# ft600.net
KiCad netlist of a schematic drawn in Altium Designer
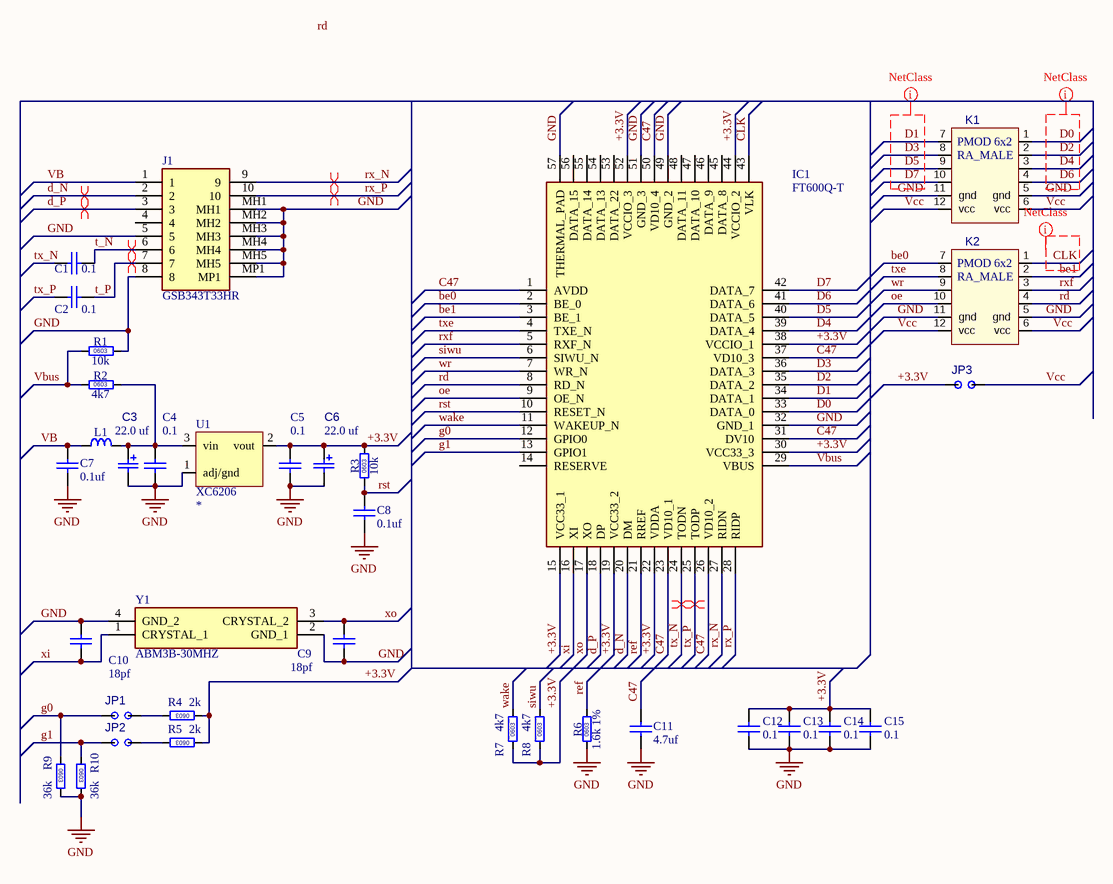
[diagram p0: ft600.SchDoc]

(export (version "E")
  (design (tool "Eeschema 10.0.6"))
  (components
    (comp (ref "C1")
      (value "0.1")
      (footprint "SM0402_3D_cap")
      (description "Capacitor  0402 inch")
      (fields (field (name "Comment") "cap0402") (field (name "PUBLISHER") "Altium Limited"))
      (libsource (lib "alt2017") (part "cap0402"))
    )
    (comp (ref "C2")
      (value "0.1")
      (footprint "SM0402_3D_cap")
      (description "Capacitor  0402 inch")
      (fields (field (name "Comment") "cap0402") (field (name "PUBLISHER") "Altium Limited"))
      (libsource (lib "alt2017") (part "cap0402"))
    )
    (comp (ref "C3")
      (value "CAP_POL_SMA")
      (footprint "CAP_POL_SMA (3216)")
      (description "CAP_POL_SMA(3216)")
      (fields (field (name "ALTIUM_UNNAMED_1") "22.0 uf"))
      (libsource (lib "alt2017") (part "CAP_POL_SMA"))
    )
    (comp (ref "C4")
      (value "0.1")
      (footprint "SM0603 _3D_cap")
      (description "Capacitor  0603 inch")
      (fields (field (name "Comment") "cap0603") (field (name "PUBLISHER") "Altium Limited"))
      (libsource (lib "alt2017") (part "cap0603"))
    )
    (comp (ref "C5")
      (value "0.1")
      (footprint "SM0603 _3D_cap")
      (description "Capacitor  0603 inch")
      (fields (field (name "Comment") "cap0603") (field (name "PUBLISHER") "Altium Limited"))
      (libsource (lib "alt2017") (part "cap0603"))
    )
    (comp (ref "C6")
      (value "CAP_POL_SMA")
      (footprint "CAP_POL_SMA (3216)")
      (description "CAP_POL_SMA(3216)")
      (fields (field (name "ALTIUM_UNNAMED_1") "22.0 uf"))
      (libsource (lib "alt2017") (part "CAP_POL_SMA"))
    )
    (comp (ref "C7")
      (value "0.1uf")
      (footprint "SM0603 _3D_cap")
      (description "Capacitor  0603 inch")
      (fields (field (name "Comment") "cap0603") (field (name "PUBLISHER") "Altium Limited"))
      (libsource (lib "alt2017") (part "cap0603"))
    )
    (comp (ref "C8")
      (value "0.1uf")
      (footprint "SM0603 _3D_cap")
      (description "Capacitor  0603 inch")
      (fields (field (name "Comment") "cap0603") (field (name "PUBLISHER") "Altium Limited"))
      (libsource (lib "alt2017") (part "cap0603"))
    )
    (comp (ref "C9")
      (value "18pf")
      (footprint "SM0603 _3D_cap")
      (description "Capacitor  0603 inch")
      (fields (field (name "Comment") "cap0603") (field (name "PUBLISHER") "Altium Limited"))
      (libsource (lib "alt2017") (part "cap0603"))
    )
    (comp (ref "C10")
      (value "18pf")
      (footprint "SM0603 _3D_cap")
      (description "Capacitor  0603 inch")
      (fields (field (name "Comment") "cap0603") (field (name "PUBLISHER") "Altium Limited"))
      (libsource (lib "alt2017") (part "cap0603"))
    )
    (comp (ref "C11")
      (value "4.7uf")
      (footprint "SM0603 _3D_cap")
      (description "Capacitor  0603 inch")
      (fields (field (name "Comment") "cap0603") (field (name "PUBLISHER") "Altium Limited"))
      (libsource (lib "alt2017") (part "cap0603"))
    )
    (comp (ref "C12")
      (value "0.1")
      (footprint "SM0603 _3D_cap")
      (description "Capacitor  0603 inch")
      (fields (field (name "Comment") "cap0603") (field (name "PUBLISHER") "Altium Limited"))
      (libsource (lib "alt2017") (part "cap0603"))
    )
    (comp (ref "C13")
      (value "0.1")
      (footprint "SM0603 _3D_cap")
      (description "Capacitor  0603 inch")
      (fields (field (name "Comment") "cap0603") (field (name "PUBLISHER") "Altium Limited"))
      (libsource (lib "alt2017") (part "cap0603"))
    )
    (comp (ref "C14")
      (value "0.1")
      (footprint "SM0603 _3D_cap")
      (description "Capacitor  0603 inch")
      (fields (field (name "Comment") "cap0603") (field (name "PUBLISHER") "Altium Limited"))
      (libsource (lib "alt2017") (part "cap0603"))
    )
    (comp (ref "C15")
      (value "0.1")
      (footprint "SM0603 _3D_cap")
      (description "Capacitor  0603 inch")
      (fields (field (name "Comment") "cap0603") (field (name "PUBLISHER") "Altium Limited"))
      (libsource (lib "alt2017") (part "cap0603"))
    )
    (comp (ref "IC1")
      (value "FT600Q-T")
      (footprint "SamacSys:QFN40P700X700X90-57N-D")
      (description "Integrated Circuit")
      (fields (field (name "MOUSER PART NUMBER") "895-FT600Q-T"))
      (libsource (lib "*") (part "FT600Q-T"))
    )
    (comp (ref "J1")
      (value "GSB343T33HR")
      (footprint "SamacSys:GSB343T33HR")
      (description "Connector")
      (fields (field (name "MOUSER PART NUMBER") "523-GSB343T33HR"))
      (libsource (lib "*") (part "GSB343T33HR"))
    )
    (comp (ref "JP1") (value "JUMPER2") (footprint "JUMPER2") (libsource (lib "alt2017") (part "JUMPER2")))
    (comp (ref "JP2") (value "JUMPER2") (footprint "JUMPER2") (libsource (lib "alt2017") (part "JUMPER2")))
    (comp (ref "JP3") (value "JUMPER2") (footprint "JUMPER2") (libsource (lib "alt2017") (part "JUMPER2")))
    (comp (ref "K1")
      (value "PMOD_6x2_ra_male")
      (footprint "PMOD_6x2_right_ANGLE")
      (description "PMOD_6x2_right_angle")
      (libsource (lib "alt2017") (part "PMOD_6x2_ra_male"))
    )
    (comp (ref "K2")
      (value "PMOD_6x2_ra_male")
      (footprint "PMOD_6x2_right_ANGLE")
      (description "PMOD_6x2_right_angle")
      (libsource (lib "alt2017") (part "PMOD_6x2_ra_male"))
    )
    (comp (ref "L1")
      (value "75R@100MHz")
      (footprint "SM0603_3D_res")
      (description "chip inductance 0603")
      (fields
        (field (name "PART NUMBER") "IND0805_MURATA_BLM21BB750SN1D")
        (field (name "POWER") "700mA")
        (field (name "AUTHOR") "S. Jafar")
      )
      (libsource (lib "alt_vovan") (part "chip inductance 0603"))
    )
    (comp (ref "R1")
      (value "10k")
      (footprint "SM0603_3D_res")
      (description "Res_0603_EU")
      (fields
        (field (name "PART NUMBER") "R1206_4K7_1%_0.25W_100PPM")
        (field (name "POWER") "0.25W")
        (field (name "AUTHOR") "CERN DEM JLC")
      )
      (libsource (lib "alt_vovan") (part "Res_0603_EU"))
    )
    (comp (ref "R2")
      (value "4k7")
      (footprint "SM0603_3D_res")
      (description "Res_0603_EU")
      (fields
        (field (name "PART NUMBER") "R1206_4K7_1%_0.25W_100PPM")
        (field (name "POWER") "0.25W")
        (field (name "AUTHOR") "CERN DEM JLC")
      )
      (libsource (lib "alt_vovan") (part "Res_0603_EU"))
    )
    (comp (ref "R3")
      (value "10k")
      (footprint "SM0603_3D_res")
      (description "Res_0603_EU")
      (fields
        (field (name "PART NUMBER") "R1206_4K7_1%_0.25W_100PPM")
        (field (name "POWER") "0.25W")
        (field (name "AUTHOR") "CERN DEM JLC")
      )
      (libsource (lib "alt_vovan") (part "Res_0603_EU"))
    )
    (comp (ref "R4")
      (value "2k")
      (footprint "SM0603_3D_res")
      (description "Res_0603_EU")
      (fields
        (field (name "PART NUMBER") "R1206_4K7_1%_0.25W_100PPM")
        (field (name "POWER") "0.25W")
        (field (name "AUTHOR") "CERN DEM JLC")
      )
      (libsource (lib "alt_vovan") (part "Res_0603_EU"))
    )
    (comp (ref "R5")
      (value "2k")
      (footprint "SM0603_3D_res")
      (description "Res_0603_EU")
      (fields
        (field (name "PART NUMBER") "R1206_4K7_1%_0.25W_100PPM")
        (field (name "POWER") "0.25W")
        (field (name "AUTHOR") "CERN DEM JLC")
      )
      (libsource (lib "alt_vovan") (part "Res_0603_EU"))
    )
    (comp (ref "R6")
      (value "1.6k 1%")
      (footprint "SM0603_3D_res")
      (description "Res_0603_EU")
      (fields
        (field (name "PART NUMBER") "R1206_4K7_1%_0.25W_100PPM")
        (field (name "POWER") "0.25W")
        (field (name "AUTHOR") "CERN DEM JLC")
      )
      (libsource (lib "alt_vovan") (part "Res_0603_EU"))
    )
    (comp (ref "R7")
      (value "4k7")
      (footprint "SM0603_3D_res")
      (description "Res_0603_EU")
      (fields
        (field (name "PART NUMBER") "R1206_4K7_1%_0.25W_100PPM")
        (field (name "POWER") "0.25W")
        (field (name "AUTHOR") "CERN DEM JLC")
      )
      (libsource (lib "alt_vovan") (part "Res_0603_EU"))
    )
    (comp (ref "R8")
      (value "4k7")
      (footprint "SM0603_3D_res")
      (description "Res_0603_EU")
      (fields
        (field (name "PART NUMBER") "R1206_4K7_1%_0.25W_100PPM")
        (field (name "POWER") "0.25W")
        (field (name "AUTHOR") "CERN DEM JLC")
      )
      (libsource (lib "alt_vovan") (part "Res_0603_EU"))
    )
    (comp (ref "R9")
      (value "36k")
      (footprint "SM0603_3D_res")
      (description "Res_0603_EU")
      (fields
        (field (name "PART NUMBER") "R1206_4K7_1%_0.25W_100PPM")
        (field (name "POWER") "0.25W")
        (field (name "AUTHOR") "CERN DEM JLC")
      )
      (libsource (lib "alt_vovan") (part "Res_0603_EU"))
    )
    (comp (ref "R10")
      (value "36k")
      (footprint "SM0603_3D_res")
      (description "Res_0603_EU")
      (fields
        (field (name "PART NUMBER") "R1206_4K7_1%_0.25W_100PPM")
        (field (name "POWER") "0.25W")
        (field (name "AUTHOR") "CERN DEM JLC")
      )
      (libsource (lib "alt_vovan") (part "Res_0603_EU"))
    )
    (comp (ref "U1")
      (value "XC6206")
      (footprint "SOT-23")
      (description "SOT-23-3 ldo")
      (fields (field (name "ALTIUM_UNNAMED_1") "*"))
      (libsource (lib "alt2017") (part "XC6206"))
    )
    (comp (ref "Y1")
      (value "ABM3B-30MHZ")
      (footprint "SamacSys:ABM3B")
      (description "Crystal or Oscillator")
      (fields
        (field (name "MANUFACTURER_PART_NUMBER") "ABM3B-11.0592MHZ-10-1-U-T")
        (field (name "MOUSER PART NUMBER") "815-ABM3B-11.0592-T")
      )
      (libsource (lib "*") (part "ABM3B-11.0592MHZ-10-1-U-T"))
    )
  )
  (nets
    (net (code "1") (name "/+3.3V") (class "Default")
      (node (ref "C12") (pin "2") (pinfunction "2_2") (pintype "passive"))
      (node (ref "C13") (pin "2") (pinfunction "2_2") (pintype "passive"))
      (node (ref "C14") (pin "2") (pinfunction "2_2") (pintype "passive"))
      (node (ref "C15") (pin "2") (pinfunction "2_2") (pintype "passive"))
      (node (ref "C5") (pin "2") (pinfunction "2_2") (pintype "passive"))
      (node (ref "C6") (pin "1") (pinfunction "a_1") (pintype "passive"))
      (node (ref "IC1") (pin "15") (pinfunction "VCC33_1_15") (pintype "passive"))
      (node (ref "IC1") (pin "19") (pinfunction "VCC33_2_19") (pintype "passive"))
      (node (ref "IC1") (pin "22") (pinfunction "VDDA_22") (pintype "passive"))
      (node (ref "IC1") (pin "30") (pinfunction "VCC33_3_30") (pintype "passive"))
      (node (ref "IC1") (pin "38") (pinfunction "VCCIO_1_38") (pintype "passive"))
      (node (ref "IC1") (pin "44") (pinfunction "VCCIO_2_44") (pintype "passive"))
      (node (ref "IC1") (pin "52") (pinfunction "VCCIO_3_52") (pintype "passive"))
      (node (ref "JP3") (pin "2") (pinfunction "2_2") (pintype "passive"))
      (node (ref "R3") (pin "2") (pinfunction "2_2") (pintype "passive"))
      (node (ref "R4") (pin "1") (pinfunction "1_1") (pintype "passive"))
      (node (ref "R5") (pin "1") (pinfunction "1_1") (pintype "passive"))
      (node (ref "R7") (pin "1") (pinfunction "1_1") (pintype "passive"))
      (node (ref "R8") (pin "1") (pinfunction "1_1") (pintype "passive"))
      (node (ref "U1") (pin "2") (pinfunction "vout_2") (pintype "passive"))
    )
    (net (code "2") (name "/C47") (class "Default")
      (node (ref "C11") (pin "2") (pinfunction "2_2") (pintype "passive"))
      (node (ref "IC1") (pin "1") (pinfunction "AVDD_1") (pintype "passive"))
      (node (ref "IC1") (pin "23") (pinfunction "VD10_1_23") (pintype "passive"))
      (node (ref "IC1") (pin "26") (pinfunction "VD10_2_26") (pintype "passive"))
      (node (ref "IC1") (pin "31") (pinfunction "DV10_31") (pintype "passive"))
      (node (ref "IC1") (pin "37") (pinfunction "VD10_3_37") (pintype "passive"))
      (node (ref "IC1") (pin "50") (pinfunction "VD10_4_50") (pintype "passive"))
    )
    (net (code "3") (name "/CLK") (class "Default")
      (node (ref "IC1") (pin "43") (pinfunction "VLK_43") (pintype "passive"))
      (node (ref "K2") (pin "1") (pinfunction "1_1") (pintype "passive"))
    )
    (net (code "4") (name "/D0") (class "Default")
      (node (ref "IC1") (pin "33") (pinfunction "DATA_0_33") (pintype "passive"))
      (node (ref "K1") (pin "1") (pinfunction "1_1") (pintype "passive"))
    )
    (net (code "5") (name "/D1") (class "Default")
      (node (ref "IC1") (pin "34") (pinfunction "DATA_1_34") (pintype "passive"))
      (node (ref "K1") (pin "7") (pinfunction "7_7") (pintype "passive"))
    )
    (net (code "6") (name "/D2") (class "Default")
      (node (ref "IC1") (pin "35") (pinfunction "DATA_2_35") (pintype "passive"))
      (node (ref "K1") (pin "2") (pinfunction "2_2") (pintype "passive"))
    )
    (net (code "7") (name "/D3") (class "Default")
      (node (ref "IC1") (pin "36") (pinfunction "DATA_3_36") (pintype "passive"))
      (node (ref "K1") (pin "8") (pinfunction "8_8") (pintype "passive"))
    )
    (net (code "8") (name "/D4") (class "Default")
      (node (ref "IC1") (pin "39") (pinfunction "DATA_4_39") (pintype "passive"))
      (node (ref "K1") (pin "3") (pinfunction "3_3") (pintype "passive"))
    )
    (net (code "9") (name "/D5") (class "Default")
      (node (ref "IC1") (pin "40") (pinfunction "DATA_5_40") (pintype "passive"))
      (node (ref "K1") (pin "9") (pinfunction "9_9") (pintype "passive"))
    )
    (net (code "10") (name "/D6") (class "Default")
      (node (ref "IC1") (pin "41") (pinfunction "DATA_6_41") (pintype "passive"))
      (node (ref "K1") (pin "4") (pinfunction "4_4") (pintype "passive"))
    )
    (net (code "11") (name "/D7") (class "Default")
      (node (ref "IC1") (pin "42") (pinfunction "DATA_7_42") (pintype "passive"))
      (node (ref "K1") (pin "10") (pinfunction "10_10") (pintype "passive"))
    )
    (net (code "12") (name "/VB") (class "Default")
      (node (ref "C7") (pin "2") (pinfunction "2_2") (pintype "passive"))
      (node (ref "J1") (pin "1") (pinfunction "1_1") (pintype "passive"))
      (node (ref "L1") (pin "1") (pinfunction "1_1") (pintype "passive"))
    )
    (net (code "13") (name "/Vbus") (class "Default")
      (node (ref "IC1") (pin "29") (pinfunction "VBUS_29") (pintype "passive"))
      (node (ref "R1") (pin "1") (pinfunction "1_1") (pintype "passive"))
      (node (ref "R2") (pin "1") (pinfunction "1_1") (pintype "passive"))
    )
    (net (code "14") (name "/Vcc") (class "Default")
      (node (ref "JP3") (pin "1") (pinfunction "1_1") (pintype "passive"))
      (node (ref "K1") (pin "12") (pinfunction "vcc_12") (pintype "passive"))
      (node (ref "K1") (pin "6") (pinfunction "vcc_6") (pintype "passive"))
      (node (ref "K2") (pin "12") (pinfunction "vcc_12") (pintype "passive"))
      (node (ref "K2") (pin "6") (pinfunction "vcc_6") (pintype "passive"))
    )
    (net (code "15") (name "/be0") (class "Default")
      (node (ref "IC1") (pin "2") (pinfunction "BE_0_2") (pintype "passive"))
      (node (ref "K2") (pin "7") (pinfunction "7_7") (pintype "passive"))
    )
    (net (code "16") (name "/be1") (class "Default")
      (node (ref "IC1") (pin "3") (pinfunction "BE_1_3") (pintype "passive"))
      (node (ref "K2") (pin "2") (pinfunction "2_2") (pintype "passive"))
    )
    (net (code "17") (name "/d_N") (class "Default")
      (node (ref "IC1") (pin "20") (pinfunction "DM_20") (pintype "passive"))
      (node (ref "J1") (pin "2") (pinfunction "2_2") (pintype "passive"))
    )
    (net (code "18") (name "/d_P") (class "Default")
      (node (ref "IC1") (pin "18") (pinfunction "DP_18") (pintype "passive"))
      (node (ref "J1") (pin "3") (pinfunction "3_3") (pintype "passive"))
    )
    (net (code "19") (name "/g0") (class "Default")
      (node (ref "IC1") (pin "12") (pinfunction "GPIO0_12") (pintype "passive"))
      (node (ref "JP1") (pin "2") (pinfunction "2_2") (pintype "passive"))
      (node (ref "R9") (pin "1") (pinfunction "1_1") (pintype "passive"))
    )
    (net (code "20") (name "/g1") (class "Default")
      (node (ref "IC1") (pin "13") (pinfunction "GPIO1_13") (pintype "passive"))
      (node (ref "JP2") (pin "2") (pinfunction "2_2") (pintype "passive"))
      (node (ref "R10") (pin "1") (pinfunction "1_1") (pintype "passive"))
    )
    (net (code "21") (name "/oe") (class "Default")
      (node (ref "IC1") (pin "9") (pinfunction "OE_N_9") (pintype "passive"))
      (node (ref "K2") (pin "10") (pinfunction "10_10") (pintype "passive"))
    )
    (net (code "22") (name "/rd") (class "Default")
      (node (ref "IC1") (pin "8") (pinfunction "RD_N_8") (pintype "passive"))
      (node (ref "K2") (pin "4") (pinfunction "4_4") (pintype "passive"))
    )
    (net (code "23") (name "/ref") (class "Default")
      (node (ref "IC1") (pin "21") (pinfunction "RREF_21") (pintype "passive"))
      (node (ref "R6") (pin "2") (pinfunction "2_2") (pintype "passive"))
    )
    (net (code "24") (name "/rst") (class "Default")
      (node (ref "C8") (pin "2") (pinfunction "2_2") (pintype "passive"))
      (node (ref "IC1") (pin "10") (pinfunction "RESET_N_10") (pintype "passive"))
      (node (ref "R3") (pin "1") (pinfunction "1_1") (pintype "passive"))
    )
    (net (code "25") (name "/rx_N") (class "Default")
      (node (ref "IC1") (pin "27") (pinfunction "RIDN_27") (pintype "passive"))
      (node (ref "J1") (pin "9") (pinfunction "9_9") (pintype "passive"))
    )
    (net (code "26") (name "/rx_P") (class "Default")
      (node (ref "IC1") (pin "28") (pinfunction "RIDP_28") (pintype "passive"))
      (node (ref "J1") (pin "10") (pinfunction "10_10") (pintype "passive"))
    )
    (net (code "27") (name "/rxf") (class "Default")
      (node (ref "IC1") (pin "5") (pinfunction "RXF_N_5") (pintype "passive"))
      (node (ref "K2") (pin "3") (pinfunction "3_3") (pintype "passive"))
    )
    (net (code "28") (name "/siwu") (class "Default")
      (node (ref "IC1") (pin "6") (pinfunction "SIWU_N_6") (pintype "passive"))
      (node (ref "R8") (pin "2") (pinfunction "2_2") (pintype "passive"))
    )
    (net (code "29") (name "/t_N") (class "Default")
      (node (ref "C1") (pin "1") (pinfunction "1_1") (pintype "passive"))
      (node (ref "J1") (pin "6") (pinfunction "6_6") (pintype "passive"))
    )
    (net (code "30") (name "/t_P") (class "Default")
      (node (ref "C2") (pin "1") (pinfunction "1_1") (pintype "passive"))
      (node (ref "J1") (pin "7") (pinfunction "7_7") (pintype "passive"))
    )
    (net (code "31") (name "/tx_N") (class "Default")
      (node (ref "C1") (pin "2") (pinfunction "2_2") (pintype "passive"))
      (node (ref "IC1") (pin "24") (pinfunction "TODN_24") (pintype "passive"))
    )
    (net (code "32") (name "/tx_P") (class "Default")
      (node (ref "C2") (pin "2") (pinfunction "2_2") (pintype "passive"))
      (node (ref "IC1") (pin "25") (pinfunction "TODP_25") (pintype "passive"))
    )
    (net (code "33") (name "/txe") (class "Default")
      (node (ref "IC1") (pin "4") (pinfunction "TXE_N_4") (pintype "passive"))
      (node (ref "K2") (pin "8") (pinfunction "8_8") (pintype "passive"))
    )
    (net (code "34") (name "/wake") (class "Default")
      (node (ref "IC1") (pin "11") (pinfunction "WAKEUP_N_11") (pintype "passive"))
      (node (ref "R7") (pin "2") (pinfunction "2_2") (pintype "passive"))
    )
    (net (code "35") (name "/wr") (class "Default")
      (node (ref "IC1") (pin "7") (pinfunction "WR_N_7") (pintype "passive"))
      (node (ref "K2") (pin "9") (pinfunction "9_9") (pintype "passive"))
    )
    (net (code "36") (name "/xi") (class "Default")
      (node (ref "C10") (pin "1") (pinfunction "1_1") (pintype "passive"))
      (node (ref "IC1") (pin "16") (pinfunction "XI_16") (pintype "passive"))
      (node (ref "Y1") (pin "1") (pinfunction "CRYSTAL_1_1") (pintype "passive"))
    )
    (net (code "37") (name "/xo") (class "Default")
      (node (ref "C9") (pin "2") (pinfunction "2_2") (pintype "passive"))
      (node (ref "IC1") (pin "17") (pinfunction "XO_17") (pintype "passive"))
      (node (ref "Y1") (pin "3") (pinfunction "CRYSTAL_2_3") (pintype "passive"))
    )
    (net (code "38") (name "GND") (class "Default")
      (node (ref "C10") (pin "2") (pinfunction "2_2") (pintype "passive"))
      (node (ref "C11") (pin "1") (pinfunction "1_1") (pintype "passive"))
      (node (ref "C12") (pin "1") (pinfunction "1_1") (pintype "passive"))
      (node (ref "C13") (pin "1") (pinfunction "1_1") (pintype "passive"))
      (node (ref "C14") (pin "1") (pinfunction "1_1") (pintype "passive"))
      (node (ref "C15") (pin "1") (pinfunction "1_1") (pintype "passive"))
      (node (ref "C3") (pin "2") (pinfunction "b_2") (pintype "passive"))
      (node (ref "C4") (pin "1") (pinfunction "1_1") (pintype "passive"))
      (node (ref "C5") (pin "1") (pinfunction "1_1") (pintype "passive"))
      (node (ref "C6") (pin "2") (pinfunction "b_2") (pintype "passive"))
      (node (ref "C7") (pin "1") (pinfunction "1_1") (pintype "passive"))
      (node (ref "C8") (pin "1") (pinfunction "1_1") (pintype "passive"))
      (node (ref "C9") (pin "1") (pinfunction "1_1") (pintype "passive"))
      (node (ref "IC1") (pin "32") (pinfunction "GND_1_32") (pintype "passive"))
      (node (ref "IC1") (pin "49") (pinfunction "GND_2_49") (pintype "passive"))
      (node (ref "IC1") (pin "51") (pinfunction "GND_3_51") (pintype "passive"))
      (node (ref "IC1") (pin "57") (pinfunction "THERMAL_PAD_57") (pintype "passive"))
      (node (ref "J1") (pin "5") (pinfunction "5_5") (pintype "passive"))
      (node (ref "J1") (pin "8") (pinfunction "8_8") (pintype "passive"))
      (node (ref "J1") (pin "MH1") (pinfunction "MH1_MH1") (pintype "passive"))
      (node (ref "J1") (pin "MH2") (pinfunction "MH2_MH2") (pintype "passive"))
      (node (ref "J1") (pin "MH3") (pinfunction "MH3_MH3") (pintype "passive"))
      (node (ref "J1") (pin "MH4") (pinfunction "MH4_MH4") (pintype "passive"))
      (node (ref "J1") (pin "MH5") (pinfunction "MH5_MH5") (pintype "passive"))
      (node (ref "J1") (pin "MP1") (pinfunction "MP1_MP1") (pintype "passive"))
      (node (ref "K1") (pin "11") (pinfunction "gnd_11") (pintype "passive"))
      (node (ref "K1") (pin "5") (pinfunction "gnd_5") (pintype "passive"))
      (node (ref "K2") (pin "11") (pinfunction "gnd_11") (pintype "passive"))
      (node (ref "K2") (pin "5") (pinfunction "gnd_5") (pintype "passive"))
      (node (ref "R1") (pin "2") (pinfunction "2_2") (pintype "passive"))
      (node (ref "R10") (pin "2") (pinfunction "2_2") (pintype "passive"))
      (node (ref "R6") (pin "1") (pinfunction "1_1") (pintype "passive"))
      (node (ref "R9") (pin "2") (pinfunction "2_2") (pintype "passive"))
      (node (ref "U1") (pin "1") (pinfunction "adj/gnd_1") (pintype "passive"))
      (node (ref "Y1") (pin "2") (pinfunction "GND_1_2") (pintype "passive"))
      (node (ref "Y1") (pin "4") (pinfunction "GND_2_4") (pintype "passive"))
    )
    (net (code "39") (name "Net-(C3-a)") (class "Default")
      (node (ref "C3") (pin "1") (pinfunction "a_1") (pintype "passive"))
      (node (ref "C4") (pin "2") (pinfunction "2_2") (pintype "passive"))
      (node (ref "L1") (pin "2") (pinfunction "2_2") (pintype "passive"))
      (node (ref "R2") (pin "2") (pinfunction "2_2") (pintype "passive"))
      (node (ref "U1") (pin "3") (pinfunction "vin_3") (pintype "passive"))
    )
    (net (code "40") (name "Net-(JP1-Pad1)") (class "Default")
      (node (ref "JP1") (pin "1") (pinfunction "1_1") (pintype "passive"))
      (node (ref "R4") (pin "2") (pinfunction "2_2") (pintype "passive"))
    )
    (net (code "41") (name "Net-(JP2-Pad1)") (class "Default")
      (node (ref "JP2") (pin "1") (pinfunction "1_1") (pintype "passive"))
      (node (ref "R5") (pin "2") (pinfunction "2_2") (pintype "passive"))
    )
    (net (code "42") (name "unconnected-(IC1-DATA_8-Pad45)") (class "Default")
      (node (ref "IC1") (pin "45") (pinfunction "DATA_8_45") (pintype "passive"))
    )
    (net (code "43") (name "unconnected-(IC1-DATA_9-Pad46)") (class "Default")
      (node (ref "IC1") (pin "46") (pinfunction "DATA_9_46") (pintype "passive"))
    )
    (net (code "44") (name "unconnected-(IC1-DATA_10-Pad47)") (class "Default")
      (node (ref "IC1") (pin "47") (pinfunction "DATA_10_47") (pintype "passive"))
    )
    (net (code "45") (name "unconnected-(IC1-DATA_11-Pad48)") (class "Default")
      (node (ref "IC1") (pin "48") (pinfunction "DATA_11_48") (pintype "passive"))
    )
    (net (code "46") (name "unconnected-(IC1-DATA_13-Pad54)") (class "Default")
      (node (ref "IC1") (pin "54") (pinfunction "DATA_13_54") (pintype "passive"))
    )
    (net (code "47") (name "unconnected-(IC1-DATA_14-Pad55)") (class "Default")
      (node (ref "IC1") (pin "55") (pinfunction "DATA_14_55") (pintype "passive"))
    )
    (net (code "48") (name "unconnected-(IC1-DATA_15-Pad56)") (class "Default")
      (node (ref "IC1") (pin "56") (pinfunction "DATA_15_56") (pintype "passive"))
    )
    (net (code "49") (name "unconnected-(IC1-DATA_22-Pad53)") (class "Default")
      (node (ref "IC1") (pin "53") (pinfunction "DATA_22_53") (pintype "passive"))
    )
    (net (code "50") (name "unconnected-(IC1-RESERVE-Pad14)") (class "Default")
      (node (ref "IC1") (pin "14") (pinfunction "RESERVE_14") (pintype "passive"))
    )
    (net (code "51") (name "unconnected-(J1-Pad4)") (class "Default")
      (node (ref "J1") (pin "4") (pinfunction "4_4") (pintype "passive"))
    )
  )
)
